# LoRaLo_V20-1.net
KiCad netlist of a schematic drawn in EAGLE
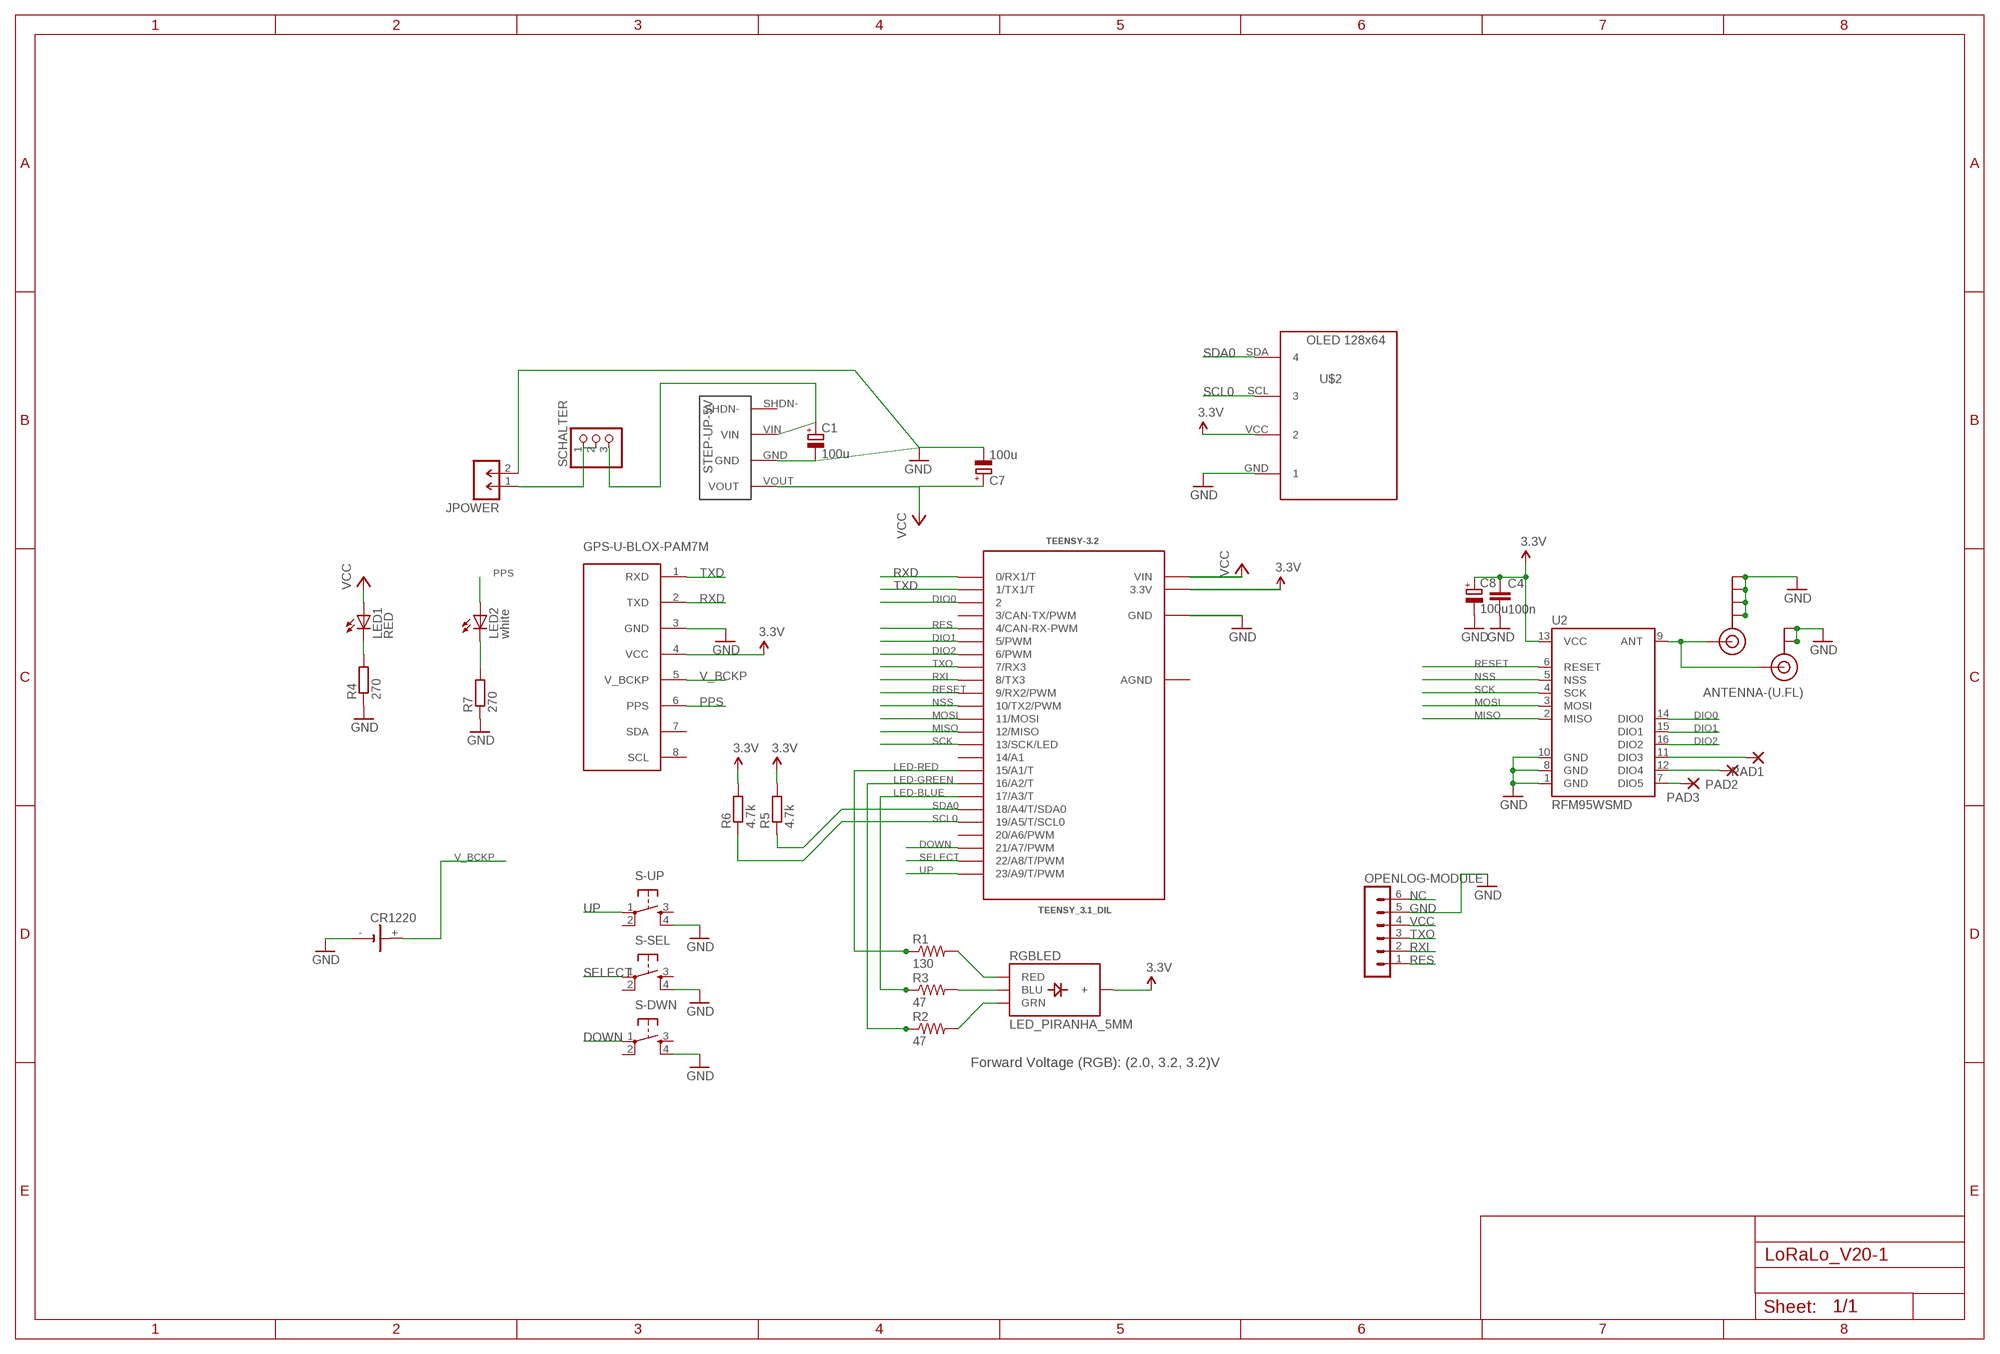
[diagram p0: schematic, sheet 1]

(export (version "E")
  (design (tool "Eeschema 10.0.6"))
  (components
    (comp (ref "ANTENNA-(EDGE-MOUNT)")
      (value "SMA_EDGE")
      (footprint "eagle-import:SMA-EDGE")
      (libsource (lib "eagle-import") (part "SMA_EDGE"))
    )
    (comp (ref "ANTENNA-(U.FL)")
      (value "U.FL")
      (footprint "eagle-import:U.FL")
      (libsource (lib "eagle-import") (part "U.FL"))
    )
    (comp (ref "C1")
      (value "100u")
      (footprint "eagle-import:PANASONIC_D")
      (libsource (lib "eagle-import") (part "CPOL-EUD"))
    )
    (comp (ref "C4")
      (value "100n")
      (footprint "eagle-import:C1206")
      (libsource (lib "eagle-import") (part "C-EUC1206"))
    )
    (comp (ref "C7")
      (value "100u")
      (footprint "eagle-import:PANASONIC_D")
      (libsource (lib "eagle-import") (part "CPOL-EUD"))
    )
    (comp (ref "C8")
      (value "100u")
      (footprint "eagle-import:PANASONIC_D")
      (libsource (lib "eagle-import") (part "CPOL-EUD"))
    )
    (comp (ref "CR1220")
      (value "CH291-1220LF")
      (footprint "eagle-import:CH291-1220LF")
      (libsource (lib "eagle-import") (part "CH291-1220LF"))
    )
    (comp (ref "GPS-U-BLOX-PAM7M")
      (value "U-BLOX-PAM-7Q")
      (footprint "eagle-import:U-BLOX-PAM-7Q")
      (libsource (lib "eagle-import") (part "U-BLOX-PAM-7Q"))
    )
    (comp (ref "JPOWER")
      (value "M-1X02-SIP-100-40")
      (footprint "eagle-import:SIP-100-02-40")
      (libsource (lib "eagle-import") (part "M-1X02-SIP-100-40"))
    )
    (comp (ref "LED1")
      (value "RED")
      (footprint "eagle-import:LED-1206")
      (libsource (lib "eagle-import") (part "LED1206"))
    )
    (comp (ref "LED2")
      (value "white")
      (footprint "eagle-import:LED-1206")
      (libsource (lib "eagle-import") (part "LED1206"))
    )
    (comp (ref "OPENLOG-MODULE")
      (value "MA06-1")
      (footprint "eagle-import:MA06-1")
      (libsource (lib "eagle-import") (part "MA06-1"))
    )
    (comp (ref "PAD1")
      (value "1,6/0,8")
      (footprint "eagle-import:1,6_0,8")
      (libsource (lib "eagle-import") (part "1,6/0,8"))
    )
    (comp (ref "PAD2")
      (value "1,6/0,8")
      (footprint "eagle-import:1,6_0,8")
      (libsource (lib "eagle-import") (part "1,6/0,8"))
    )
    (comp (ref "PAD3")
      (value "1,6/0,8")
      (footprint "eagle-import:1,6_0,8")
      (libsource (lib "eagle-import") (part "1,6/0,8"))
    )
    (comp (ref "R1")
      (value "130")
      (footprint "eagle-import:1206")
      (libsource (lib "eagle-import") (part "RESISTOR1206"))
    )
    (comp (ref "R2")
      (value "47")
      (footprint "eagle-import:1206")
      (libsource (lib "eagle-import") (part "RESISTOR1206"))
    )
    (comp (ref "R3")
      (value "47")
      (footprint "eagle-import:1206")
      (libsource (lib "eagle-import") (part "RESISTOR1206"))
    )
    (comp (ref "R4")
      (value "270")
      (footprint "eagle-import:M1206")
      (libsource (lib "eagle-import") (part "R-EU_M1206"))
    )
    (comp (ref "R5")
      (value "4.7k")
      (footprint "eagle-import:M1206")
      (libsource (lib "eagle-import") (part "R-EU_M1206"))
    )
    (comp (ref "R6")
      (value "4.7k")
      (footprint "eagle-import:M1206")
      (libsource (lib "eagle-import") (part "R-EU_M1206"))
    )
    (comp (ref "R7")
      (value "270")
      (footprint "eagle-import:M1206")
      (libsource (lib "eagle-import") (part "R-EU_M1206"))
    )
    (comp (ref "RGBLED")
      (value "LED_PIRANHA_5MM")
      (footprint "eagle-import:LED_PIRANHA_5MM")
      (libsource (lib "eagle-import") (part "LED_PIRANHA_5MM"))
    )
    (comp (ref "S-DWN")
      (value "TAC_SWITCHPTH")
      (footprint "eagle-import:TACTILE-PTH")
      (libsource (lib "eagle-import") (part "TAC_SWITCHPTH"))
    )
    (comp (ref "S-SEL")
      (value "TAC_SWITCHPTH")
      (footprint "eagle-import:TACTILE-PTH")
      (libsource (lib "eagle-import") (part "TAC_SWITCHPTH"))
    )
    (comp (ref "S-UP")
      (value "TAC_SWITCHPTH")
      (footprint "eagle-import:TACTILE-PTH")
      (libsource (lib "eagle-import") (part "TAC_SWITCHPTH"))
    )
    (comp (ref "SCHALTER")
      (value "PINHD-1X3")
      (footprint "eagle-import:1X03")
      (libsource (lib "eagle-import") (part "PINHD-1X3"))
    )
    (comp (ref "STEP-UP-5V")
      (value "POLOLU_STEP-UP")
      (footprint "eagle-import:POLOLU_STEP-UP")
      (libsource (lib "eagle-import") (part "POLOLU_STEP-UP"))
    )
    (comp (ref "TEENSY-3.2")
      (value "TEENSY_3.1_DIL")
      (footprint "eagle-import:TEENSY3-DIL")
      (libsource (lib "eagle-import") (part "TEENSY_3.1_DIL"))
    )
    (comp (ref "U$2")
      (value "OLED_128X64")
      (footprint "eagle-import:OLED_128X64")
      (libsource (lib "eagle-import") (part "OLED_128X64"))
    )
    (comp (ref "U2")
      (value "RFM95WSMD")
      (footprint "eagle-import:RFM95W_SMD")
      (libsource (lib "eagle-import") (part "RFM95WSMD"))
    )
  )
  (nets
    (net (code "1") (name "/AGND") (class "Default")
      (node (ref "TEENSY-3.2") (pin "AGND") (pinfunction "AGND_AGND") (pintype "power_in"))
    )
    (net (code "2") (name "/DIO0") (class "Default")
      (node (ref "TEENSY-3.2") (pin "2") (pinfunction "2_2") (pintype "bidirectional"))
      (node (ref "U2") (pin "14") (pinfunction "DIO0_14") (pintype "input"))
    )
    (net (code "3") (name "/DIO1") (class "Default")
      (node (ref "TEENSY-3.2") (pin "5") (pinfunction "5/PWM_5") (pintype "bidirectional"))
      (node (ref "U2") (pin "15") (pinfunction "DIO1_15") (pintype "input"))
    )
    (net (code "4") (name "/DIO2") (class "Default")
      (node (ref "TEENSY-3.2") (pin "6") (pinfunction "6/PWM_6") (pintype "bidirectional"))
      (node (ref "U2") (pin "16") (pinfunction "DIO2_16") (pintype "input"))
    )
    (net (code "5") (name "/DOWN") (class "Default")
      (node (ref "S-DWN") (pin "1") (pinfunction "1_1") (pintype "passive"))
      (node (ref "TEENSY-3.2") (pin "21/A7") (pinfunction "21/A7/PWM_21/A7") (pintype "bidirectional"))
    )
    (net (code "6") (name "/LED-BLUE") (class "Default")
      (node (ref "R3") (pin "1") (pinfunction "1_1") (pintype "passive"))
      (node (ref "TEENSY-3.2") (pin "17/A3") (pinfunction "17/A3/T_17/A3") (pintype "bidirectional"))
    )
    (net (code "7") (name "/LED-GREEN") (class "Default")
      (node (ref "R2") (pin "1") (pinfunction "1_1") (pintype "passive"))
      (node (ref "TEENSY-3.2") (pin "16/A2") (pinfunction "16/A2/T_16/A2") (pintype "bidirectional"))
    )
    (net (code "8") (name "/LED-RED") (class "Default")
      (node (ref "R1") (pin "1") (pinfunction "1_1") (pintype "passive"))
      (node (ref "TEENSY-3.2") (pin "15/A1") (pinfunction "15/A1/T_15/A1") (pintype "bidirectional"))
    )
    (net (code "9") (name "/MISO") (class "Default")
      (node (ref "TEENSY-3.2") (pin "12") (pinfunction "12/MISO_12") (pintype "bidirectional"))
      (node (ref "U2") (pin "2") (pinfunction "MISO_2") (pintype "output"))
    )
    (net (code "10") (name "/MOSI") (class "Default")
      (node (ref "TEENSY-3.2") (pin "11") (pinfunction "11/MOSI_11") (pintype "bidirectional"))
      (node (ref "U2") (pin "3") (pinfunction "MOSI_3") (pintype "input"))
    )
    (net (code "11") (name "/NC") (class "Default")
      (node (ref "OPENLOG-MODULE") (pin "6") (pinfunction "6_6") (pintype "passive"))
    )
    (net (code "12") (name "/NSS") (class "Default")
      (node (ref "TEENSY-3.2") (pin "10") (pinfunction "10/TX2/PWM_10") (pintype "bidirectional"))
      (node (ref "U2") (pin "5") (pinfunction "NSS_5") (pintype "input"))
    )
    (net (code "13") (name "/PPS") (class "Default")
      (node (ref "GPS-U-BLOX-PAM7M") (pin "6") (pinfunction "PPS_6") (pintype "bidirectional"))
      (node (ref "LED2") (pin "A") (pinfunction "A_A") (pintype "passive"))
    )
    (net (code "14") (name "/RES") (class "Default")
      (node (ref "OPENLOG-MODULE") (pin "1") (pinfunction "1_1") (pintype "passive"))
      (node (ref "TEENSY-3.2") (pin "4") (pinfunction "4/CAN-RX-PWM_4") (pintype "bidirectional"))
    )
    (net (code "15") (name "/RESET") (class "Default")
      (node (ref "TEENSY-3.2") (pin "9") (pinfunction "9/RX2/PWM_9") (pintype "bidirectional"))
      (node (ref "U2") (pin "6") (pinfunction "RESET_6") (pintype "output"))
    )
    (net (code "16") (name "/RXD") (class "Default")
      (node (ref "GPS-U-BLOX-PAM7M") (pin "2") (pinfunction "TXD_2") (pintype "bidirectional"))
      (node (ref "TEENSY-3.2") (pin "0") (pinfunction "0/RX1/T_0") (pintype "bidirectional"))
    )
    (net (code "17") (name "/RXI") (class "Default")
      (node (ref "OPENLOG-MODULE") (pin "2") (pinfunction "2_2") (pintype "passive"))
      (node (ref "TEENSY-3.2") (pin "8") (pinfunction "8/TX3_8") (pintype "bidirectional"))
    )
    (net (code "18") (name "/SCK") (class "Default")
      (node (ref "TEENSY-3.2") (pin "13") (pinfunction "13/SCK/LED_13") (pintype "bidirectional"))
      (node (ref "U2") (pin "4") (pinfunction "SCK_4") (pintype "input"))
    )
    (net (code "19") (name "/SCL0") (class "Default")
      (node (ref "R6") (pin "1") (pinfunction "1_1") (pintype "passive"))
      (node (ref "TEENSY-3.2") (pin "19/A5") (pinfunction "19/A5/T/SCL0_19/A5") (pintype "bidirectional"))
      (node (ref "U$2") (pin "SCL") (pinfunction "3_SCL") (pintype "bidirectional"))
    )
    (net (code "20") (name "/SDA0") (class "Default")
      (node (ref "R5") (pin "1") (pinfunction "1_1") (pintype "passive"))
      (node (ref "TEENSY-3.2") (pin "18/A4") (pinfunction "18/A4/T/SDA0_18/A4") (pintype "bidirectional"))
      (node (ref "U$2") (pin "SDA") (pinfunction "4_SDA") (pintype "bidirectional"))
    )
    (net (code "21") (name "/SELECT") (class "Default")
      (node (ref "S-SEL") (pin "1") (pinfunction "1_1") (pintype "passive"))
      (node (ref "TEENSY-3.2") (pin "22/A8") (pinfunction "22/A8/T/PWM_22/A8") (pintype "bidirectional"))
    )
    (net (code "22") (name "/TXD") (class "Default")
      (node (ref "GPS-U-BLOX-PAM7M") (pin "1") (pinfunction "RXD_1") (pintype "bidirectional"))
      (node (ref "TEENSY-3.2") (pin "1") (pinfunction "1/TX1/T_1") (pintype "bidirectional"))
    )
    (net (code "23") (name "/TXO") (class "Default")
      (node (ref "OPENLOG-MODULE") (pin "3") (pinfunction "3_3") (pintype "passive"))
      (node (ref "TEENSY-3.2") (pin "7") (pinfunction "7/RX3_7") (pintype "bidirectional"))
    )
    (net (code "24") (name "/UP") (class "Default")
      (node (ref "S-UP") (pin "1") (pinfunction "1_1") (pintype "passive"))
      (node (ref "TEENSY-3.2") (pin "23/A9") (pinfunction "23/A9/T/PWM_23/A9") (pintype "bidirectional"))
    )
    (net (code "25") (name "/V_BCKP") (class "Default")
      (node (ref "CR1220") (pin "+") (pinfunction "+_+") (pintype "passive"))
      (node (ref "GPS-U-BLOX-PAM7M") (pin "5") (pinfunction "V_BCKP_5") (pintype "bidirectional"))
    )
    (net (code "26") (name "3.3V") (class "Default")
      (node (ref "C4") (pin "1") (pinfunction "1_1") (pintype "passive"))
      (node (ref "C8") (pin "+") (pinfunction "+_+") (pintype "passive"))
      (node (ref "GPS-U-BLOX-PAM7M") (pin "4") (pinfunction "VCC_4") (pintype "bidirectional"))
      (node (ref "R5") (pin "2") (pinfunction "2_2") (pintype "passive"))
      (node (ref "R6") (pin "2") (pinfunction "2_2") (pintype "passive"))
      (node (ref "RGBLED") (pin "+") (pinfunction "+_+") (pintype "bidirectional"))
      (node (ref "TEENSY-3.2") (pin "3.3V") (pinfunction "3.3V_3.3V") (pintype "power_in"))
      (node (ref "U$2") (pin "VCC") (pinfunction "2_VCC") (pintype "bidirectional"))
      (node (ref "U2") (pin "13") (pinfunction "VCC_13") (pintype "bidirectional"))
    )
    (net (code "27") (name "GND") (class "Default")
      (node (ref "ANTENNA-(EDGE-MOUNT)") (pin "GND@0") (pinfunction "GND_GND@0") (pintype "bidirectional"))
      (node (ref "ANTENNA-(EDGE-MOUNT)") (pin "GND@1") (pinfunction "GND_GND@1") (pintype "bidirectional"))
      (node (ref "ANTENNA-(EDGE-MOUNT)") (pin "GND@2") (pinfunction "GND_GND@2") (pintype "bidirectional"))
      (node (ref "ANTENNA-(EDGE-MOUNT)") (pin "GND@3") (pinfunction "GND_GND@3") (pintype "bidirectional"))
      (node (ref "ANTENNA-(U.FL)") (pin "P$1") (pinfunction "GND_P$1") (pintype "bidirectional"))
      (node (ref "ANTENNA-(U.FL)") (pin "P$2") (pinfunction "GND_P$2") (pintype "bidirectional"))
      (node (ref "C1") (pin "-") (pinfunction "-_-") (pintype "passive"))
      (node (ref "C4") (pin "2") (pinfunction "2_2") (pintype "passive"))
      (node (ref "C7") (pin "-") (pinfunction "-_-") (pintype "passive"))
      (node (ref "C8") (pin "-") (pinfunction "-_-") (pintype "passive"))
      (node (ref "CR1220") (pin "-") (pinfunction "-_-") (pintype "passive"))
      (node (ref "GPS-U-BLOX-PAM7M") (pin "3") (pinfunction "GND_3") (pintype "bidirectional"))
      (node (ref "JPOWER") (pin "2") (pinfunction "2_2") (pintype "passive"))
      (node (ref "OPENLOG-MODULE") (pin "5") (pinfunction "5_5") (pintype "passive"))
      (node (ref "R4") (pin "1") (pinfunction "1_1") (pintype "passive"))
      (node (ref "R7") (pin "1") (pinfunction "1_1") (pintype "passive"))
      (node (ref "S-DWN") (pin "4") (pinfunction "4_4") (pintype "passive"))
      (node (ref "S-SEL") (pin "4") (pinfunction "4_4") (pintype "passive"))
      (node (ref "S-UP") (pin "4") (pinfunction "4_4") (pintype "passive"))
      (node (ref "STEP-UP-5V") (pin "GND") (pinfunction "GND_GND") (pintype "bidirectional"))
      (node (ref "TEENSY-3.2") (pin "GND") (pinfunction "GND_GND") (pintype "power_in"))
      (node (ref "U$2") (pin "GND") (pinfunction "1_GND") (pintype "bidirectional"))
      (node (ref "U2") (pin "1") (pinfunction "GND_1") (pintype "power_in"))
      (node (ref "U2") (pin "10") (pinfunction "GND_10") (pintype "power_in"))
      (node (ref "U2") (pin "8") (pinfunction "GND_8") (pintype "power_in"))
    )
    (net (code "28") (name "Net-(ANTENNA-(EDGE-MOUNT)-SIGNAL)") (class "Default")
      (node (ref "ANTENNA-(EDGE-MOUNT)") (pin "SIG") (pinfunction "SIGNAL_SIG") (pintype "bidirectional"))
      (node (ref "ANTENNA-(U.FL)") (pin "P$3") (pinfunction "SIGNAL_P$3") (pintype "bidirectional"))
      (node (ref "U2") (pin "9") (pinfunction "ANT_9") (pintype "bidirectional"))
    )
    (net (code "29") (name "Net-(C1-Pad+)") (class "Default")
      (node (ref "C1") (pin "+") (pinfunction "+_+") (pintype "passive"))
      (node (ref "SCHALTER") (pin "3") (pinfunction "3_3") (pintype "passive"))
      (node (ref "STEP-UP-5V") (pin "VIN") (pinfunction "VIN_VIN") (pintype "bidirectional"))
    )
    (net (code "30") (name "Net-(JPOWER-Pad1)") (class "Default")
      (node (ref "JPOWER") (pin "1") (pinfunction "1_1") (pintype "passive"))
      (node (ref "SCHALTER") (pin "1") (pinfunction "1_1") (pintype "passive"))
      (node (ref "SCHALTER") (pin "2") (pinfunction "2_2") (pintype "passive"))
    )
    (net (code "31") (name "Net-(LED1-PadC)") (class "Default")
      (node (ref "LED1") (pin "C") (pinfunction "C_C") (pintype "passive"))
      (node (ref "R4") (pin "2") (pinfunction "2_2") (pintype "passive"))
    )
    (net (code "32") (name "Net-(LED2-PadC)") (class "Default")
      (node (ref "LED2") (pin "C") (pinfunction "C_C") (pintype "passive"))
      (node (ref "R7") (pin "2") (pinfunction "2_2") (pintype "passive"))
    )
    (net (code "33") (name "Net-(PAD1-P)") (class "Default")
      (node (ref "PAD1") (pin "1") (pinfunction "P_1") (pintype "passive"))
      (node (ref "U2") (pin "11") (pinfunction "DIO3_11") (pintype "bidirectional"))
    )
    (net (code "34") (name "Net-(PAD2-P)") (class "Default")
      (node (ref "PAD2") (pin "1") (pinfunction "P_1") (pintype "passive"))
      (node (ref "U2") (pin "12") (pinfunction "DIO4_12") (pintype "bidirectional"))
    )
    (net (code "35") (name "Net-(PAD3-P)") (class "Default")
      (node (ref "PAD3") (pin "1") (pinfunction "P_1") (pintype "passive"))
      (node (ref "U2") (pin "7") (pinfunction "DIO5_7") (pintype "bidirectional"))
    )
    (net (code "36") (name "Net-(RGBLED-BLU)") (class "Default")
      (node (ref "R3") (pin "2") (pinfunction "2_2") (pintype "passive"))
      (node (ref "RGBLED") (pin "B") (pinfunction "BLU_B") (pintype "bidirectional"))
    )
    (net (code "37") (name "Net-(RGBLED-GRN)") (class "Default")
      (node (ref "R2") (pin "2") (pinfunction "2_2") (pintype "passive"))
      (node (ref "RGBLED") (pin "G") (pinfunction "GRN_G") (pintype "bidirectional"))
    )
    (net (code "38") (name "Net-(RGBLED-RED)") (class "Default")
      (node (ref "R1") (pin "2") (pinfunction "2_2") (pintype "passive"))
      (node (ref "RGBLED") (pin "R") (pinfunction "RED_R") (pintype "bidirectional"))
    )
    (net (code "39") (name "VCC") (class "Default")
      (node (ref "C7") (pin "+") (pinfunction "+_+") (pintype "passive"))
      (node (ref "LED1") (pin "A") (pinfunction "A_A") (pintype "passive"))
      (node (ref "OPENLOG-MODULE") (pin "4") (pinfunction "4_4") (pintype "passive"))
      (node (ref "STEP-UP-5V") (pin "VOUT") (pinfunction "VOUT_VOUT") (pintype "bidirectional"))
      (node (ref "TEENSY-3.2") (pin "VIN") (pinfunction "VIN_VIN") (pintype "power_in"))
    )
    (net (code "40") (name "unconnected-(GPS-U-BLOX-PAM7M-SCL-Pad8)") (class "Default")
      (node (ref "GPS-U-BLOX-PAM7M") (pin "8") (pinfunction "SCL_8") (pintype "bidirectional"))
    )
    (net (code "41") (name "unconnected-(GPS-U-BLOX-PAM7M-SDA-Pad7)") (class "Default")
      (node (ref "GPS-U-BLOX-PAM7M") (pin "7") (pinfunction "SDA_7") (pintype "bidirectional"))
    )
    (net (code "42") (name "unconnected-(S-DWN-Pad2)") (class "Default")
      (node (ref "S-DWN") (pin "2") (pinfunction "2_2") (pintype "passive"))
    )
    (net (code "43") (name "unconnected-(S-DWN-Pad3)") (class "Default")
      (node (ref "S-DWN") (pin "3") (pinfunction "3_3") (pintype "passive"))
    )
    (net (code "44") (name "unconnected-(S-SEL-Pad2)") (class "Default")
      (node (ref "S-SEL") (pin "2") (pinfunction "2_2") (pintype "passive"))
    )
    (net (code "45") (name "unconnected-(S-SEL-Pad3)") (class "Default")
      (node (ref "S-SEL") (pin "3") (pinfunction "3_3") (pintype "passive"))
    )
    (net (code "46") (name "unconnected-(S-UP-Pad2)") (class "Default")
      (node (ref "S-UP") (pin "2") (pinfunction "2_2") (pintype "passive"))
    )
    (net (code "47") (name "unconnected-(S-UP-Pad3)") (class "Default")
      (node (ref "S-UP") (pin "3") (pinfunction "3_3") (pintype "passive"))
    )
    (net (code "48") (name "unconnected-(STEP-UP-5V-PadSHDN-)") (class "Default")
      (node (ref "STEP-UP-5V") (pin "SHDN-") (pinfunction "SHDN-_SHDN-") (pintype "bidirectional"))
    )
    (net (code "49") (name "unconnected-(TEENSY-3.2-3{slash}CAN-TX{slash}PWM-Pad3)") (class "Default")
      (node (ref "TEENSY-3.2") (pin "3") (pinfunction "3/CAN-TX/PWM_3") (pintype "bidirectional"))
    )
    (net (code "50") (name "unconnected-(TEENSY-3.2-14{slash}A1-Pad14{slash}A0)") (class "Default")
      (node (ref "TEENSY-3.2") (pin "14/A0") (pinfunction "14/A1_14/A0") (pintype "bidirectional"))
    )
    (net (code "51") (name "unconnected-(TEENSY-3.2-20{slash}A6{slash}PWM-Pad20{slash}A6)") (class "Default")
      (node (ref "TEENSY-3.2") (pin "20/A6") (pinfunction "20/A6/PWM_20/A6") (pintype "bidirectional"))
    )
  )
)
